# Copy_of_Power_Board.net
KiCad netlist of a schematic drawn in Altium Designer
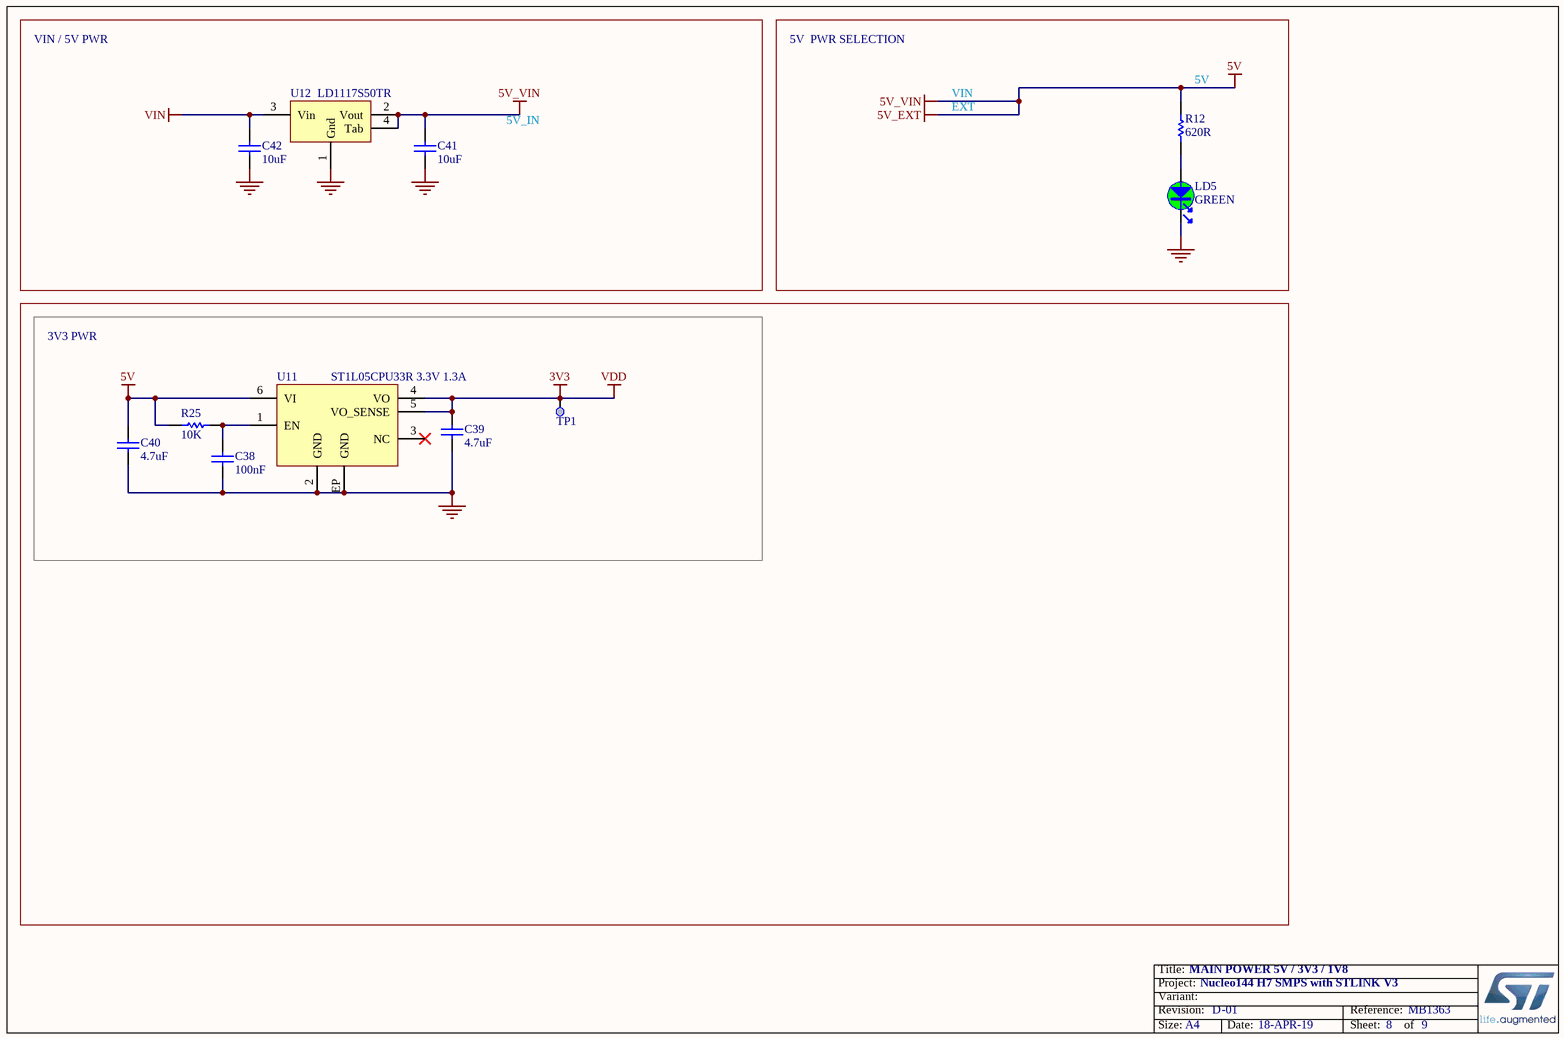
[diagram p0: Copy of Power_Board.SchDoc]

(export (version "E")
  (design (tool "Eeschema 10.0.6"))
  (components
    (comp (ref "C38")
      (value "100nF")
      (footprint "C0402")
      (description "Capacitor, MLCC, 100nF, 16V, X7R, 10%, 0402, T=0.5mm")
      (fields
        (field (name "INTERNAL_PART_NUMBER") "MCD-00006")
        (field (name "MANUFACTURER_PART_NUMBER") "CC0402KRX7R7BB104")
        (field (name "PROVIDED_BY") "SUBCO")
      )
      (libsource (lib "MCD_PARTS_database") (part "Capacitor"))
    )
    (comp (ref "C39")
      (value "4.7uF")
      (footprint "C0603")
      (description "Capacitor, MLCC, 4.7µF, 10V, X5R, 20%, 0603, T=0,8mm")
      (fields
        (field (name "INTERNAL_PART_NUMBER") "MCD-01121")
        (field (name "MANUFACTURER_PART_NUMBER") "GRM188R61A475ME15")
        (field (name "PROVIDED_BY") "SUBCO")
      )
      (libsource (lib "MCD_PARTS_database") (part "Capacitor"))
    )
    (comp (ref "C40")
      (value "4.7uF")
      (footprint "C0603")
      (description "Capacitor, MLCC, 4.7uF, 16V, X5R, 20%, 0603, T=0,8mm")
      (fields
        (field (name "INTERNAL_PART_NUMBER") "MCD-00097")
        (field (name "MANUFACTURER_PART_NUMBER") "GRM188R61C475KE11")
        (field (name "PROVIDED_BY") "SUBCO")
      )
      (libsource (lib "MCD_PARTS_database") (part "Capacitor"))
    )
    (comp (ref "C41")
      (value "10uF")
      (footprint "C0805")
      (description "Capacitor, MLCC, 10uF, 25V, X5R, 10%, 0805, T=0,85mm")
      (fields
        (field (name "INTERNAL_PART_NUMBER") "MCD-00014")
        (field (name "MANUFACTURER_PART_NUMBER") "CC0805KRX5R8BB106")
        (field (name "PROVIDED_BY") "SUBCO")
      )
      (libsource (lib "MCD_PARTS_database") (part "Capacitor"))
    )
    (comp (ref "C42")
      (value "10uF")
      (footprint "C0805")
      (description "Capacitor, MLCC, 10uF, 25V, X5R, 10%, 0805, T=0,85mm")
      (fields
        (field (name "INTERNAL_PART_NUMBER") "MCD-00014")
        (field (name "MANUFACTURER_PART_NUMBER") "CC0805KRX5R8BB106")
        (field (name "PROVIDED_BY") "SUBCO")
      )
      (libsource (lib "MCD_PARTS_database") (part "Capacitor"))
    )
    (comp (ref "LD5")
      (value "GREEN")
      (footprint "LED_0603_OSRAM_LG-Q396-PS-35_GREEN_1A2K_H0P4")
      (description "LED Green, 0603 SMD, Forward Voltage Typ=2V, Max=2.5V")
      (fields
        (field (name "INTERNAL_PART_NUMBER") "MCD-00588")
        (field (name "MANUFACTURER_PART_NUMBER") "LG Q396-PS-35")
        (field (name "PROVIDED_BY") "SUBCO")
      )
      (libsource (lib "MCD_PARTS_database") (part "LED_green"))
    )
    (comp (ref "R12")
      (value "620R")
      (footprint "R0603")
      (description "Resistor,620R,0603,1%,1/10W")
      (fields
        (field (name "INTERNAL_PART_NUMBER") "MCD-00500")
        (field (name "MANUFACTURER_PART_NUMBER") "RC0603FR-07620RL")
        (field (name "PROVIDED_BY") "SUBCO")
      )
      (libsource (lib "MCD_PARTS_database") (part "Resistor"))
    )
    (comp (ref "R25")
      (value "10K")
      (footprint "R0402")
      (description "Resistor,10K,0402,1%,1/16W")
      (fields
        (field (name "INTERNAL_PART_NUMBER") "MCD-00053")
        (field (name "MANUFACTURER_PART_NUMBER") "RC0402FR-0710KL")
        (field (name "PROVIDED_BY") "SUBCO")
      )
      (libsource (lib "MCD_PARTS_database") (part "Resistor"))
    )
    (comp (ref "TP1")
      (value "Test Point")
      (footprint "TP_SMD_1MM")
      (description "Test Point 1mm")
      (fields (field (name "INTERNAL_PART_NUMBER") "MCD-00074") (field (name "MANUFACTURER") "n/a"))
      (libsource (lib "MCD_PARTS_database") (part "Test Point"))
    )
    (comp (ref "U11")
      (value "ST1L05CPU33R 3.3V 1.3A")
      (footprint "ICC_DFN6-EPAD_3X3_P095")
      (description "LDO, 3.3V, 1.3A, Very low quiescent current BiCMOS voltage regulator")
      (fields
        (field (name "INTERNAL_PART_NUMBER") "MCD-01025")
        (field (name "MANUFACTURER_PART_NUMBER") "ST1L05CPU33R")
        (field (name "PROVIDED_BY") "SUBCO with ST control")
      )
      (libsource (lib "MCD_PARTS_database") (part "ST1L05CPU33R"))
    )
    (comp (ref "U12")
      (value "LD1117S50TR")
      (footprint "REG_SOT223-TAB")
      (description "IC REG LDO 5V 0.8A SOT223")
      (fields
        (field (name "INTERNAL_PART_NUMBER") "MCD-00088")
        (field (name "MANUFACTURER") "STMICROELECTRONICS")
        (field (name "PROVIDED_BY") "SUBCO with ST control")
      )
      (libsource (lib "MCD_PARTS_database") (part "LD1117S50TR"))
    )
  )
  (nets
    (net (code "1") (name "3V3") (class "Default")
      (node (ref "C39") (pin "2") (pinfunction "2_2") (pintype "passive"))
      (node (ref "TP1") (pin "1") (pinfunction "1_1") (pintype "passive"))
      (node (ref "U11") (pin "4") (pinfunction "VO_4") (pintype "passive"))
      (node (ref "U11") (pin "5") (pinfunction "VO_SENSE_5") (pintype "passive"))
    )
    (net (code "2") (name "5V") (class "Default")
      (node (ref "C40") (pin "2") (pinfunction "2_2") (pintype "passive"))
      (node (ref "C41") (pin "2") (pinfunction "2_2") (pintype "passive"))
      (node (ref "R12") (pin "2") (pinfunction "2_2") (pintype "passive"))
      (node (ref "R25") (pin "2") (pinfunction "2_2") (pintype "passive"))
      (node (ref "U11") (pin "6") (pinfunction "VI_6") (pintype "passive"))
      (node (ref "U12") (pin "2") (pinfunction "Vout_2") (pintype "passive"))
      (node (ref "U12") (pin "4") (pinfunction "Tab_4") (pintype "passive"))
    )
    (net (code "3") (name "GND") (class "Default")
      (node (ref "C38") (pin "2") (pinfunction "2_2") (pintype "passive"))
      (node (ref "C39") (pin "1") (pinfunction "1_1") (pintype "passive"))
      (node (ref "C40") (pin "1") (pinfunction "1_1") (pintype "passive"))
      (node (ref "C41") (pin "1") (pinfunction "1_1") (pintype "passive"))
      (node (ref "C42") (pin "1") (pinfunction "1_1") (pintype "passive"))
      (node (ref "LD5") (pin "2") (pintype "passive"))
      (node (ref "U11") (pin "2") (pinfunction "GND_2") (pintype "passive"))
      (node (ref "U11") (pin "EP") (pinfunction "GND_EP") (pintype "passive"))
      (node (ref "U12") (pin "1") (pinfunction "Gnd_1") (pintype "passive"))
    )
    (net (code "4") (name "Net-(LD5-Pad1)") (class "Default")
      (node (ref "LD5") (pin "1") (pintype "passive"))
      (node (ref "R12") (pin "1") (pinfunction "1_1") (pintype "passive"))
    )
    (net (code "5") (name "Net-(U11-EN)") (class "Default")
      (node (ref "C38") (pin "1") (pinfunction "1_1") (pintype "passive"))
      (node (ref "R25") (pin "1") (pinfunction "1_1") (pintype "passive"))
      (node (ref "U11") (pin "1") (pinfunction "EN_1") (pintype "passive"))
    )
    (net (code "6") (name "VIN") (class "Default")
      (node (ref "C42") (pin "2") (pinfunction "2_2") (pintype "passive"))
      (node (ref "U12") (pin "3") (pinfunction "Vin_3") (pintype "passive"))
    )
    (net (code "7") (name "unconnected-(U11-NC-Pad3)") (class "Default")
      (node (ref "U11") (pin "3") (pinfunction "NC_3") (pintype "passive+no_connect"))
    )
  )
)
